# Bpod_Input.net
KiCad netlist of a schematic drawn in Altium Designer
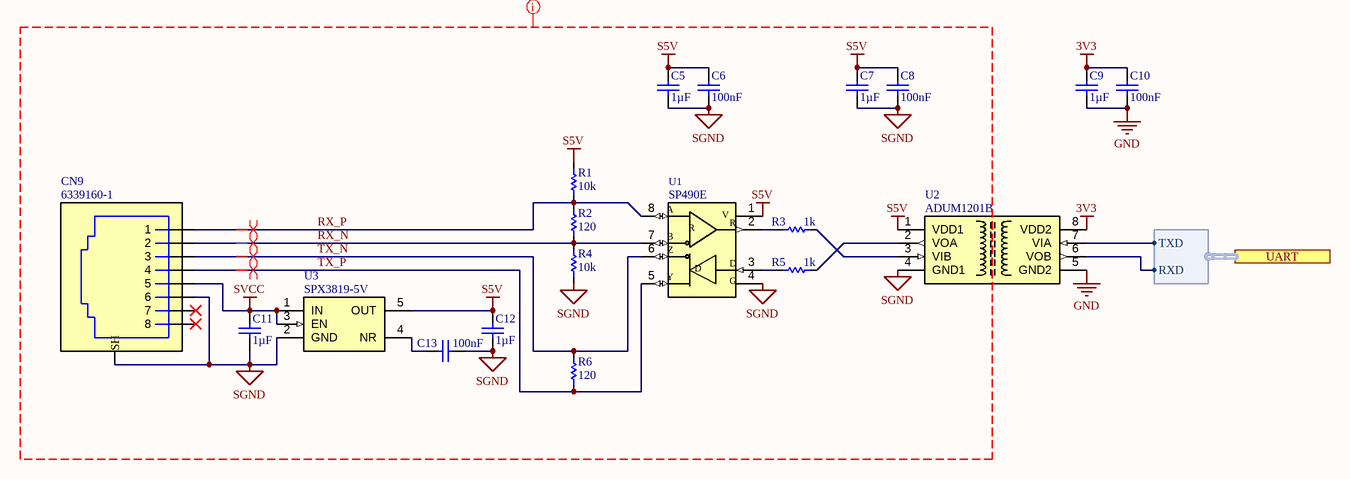
[diagram p0: Bpod Input.SchDoc]

(export (version "E")
  (design (tool "Eeschema 10.0.6"))
  (components
    (comp (ref "C5")
      (value "1µF")
      (footprint "CAP_CHIP_0603")
      (description "0603 Multilayer Ceramic Capacitors MLCC")
      (fields (field (name "PARTNUMBER") "CL10A105KB8NNNC") (field (name "TOLERANCE") "10%"))
      (libsource (lib "Sainsbury Wellcome Centre") (part "Cap"))
    )
    (comp (ref "C6")
      (value "100nF")
      (footprint "CAP_CHIP_0603")
      (description "0603 Multilayer Ceramic Capacitors MLCC")
      (fields (field (name "PARTNUMBER") "CC0603KRX7R9BB104") (field (name "TOLERANCE") "10%"))
      (libsource (lib "Sainsbury Wellcome Centre") (part "Cap"))
    )
    (comp (ref "C7")
      (value "1µF")
      (footprint "CAP_CHIP_0603")
      (description "0603 Multilayer Ceramic Capacitors MLCC")
      (fields (field (name "PARTNUMBER") "CL10A105KB8NNNC") (field (name "TOLERANCE") "10%"))
      (libsource (lib "Sainsbury Wellcome Centre") (part "Cap"))
    )
    (comp (ref "C8")
      (value "100nF")
      (footprint "CAP_CHIP_0603")
      (description "0603 Multilayer Ceramic Capacitors MLCC")
      (fields (field (name "PARTNUMBER") "CC0603KRX7R9BB104") (field (name "TOLERANCE") "10%"))
      (libsource (lib "Sainsbury Wellcome Centre") (part "Cap"))
    )
    (comp (ref "C9")
      (value "1µF")
      (footprint "CAP_CHIP_0603")
      (description "0603 Multilayer Ceramic Capacitors MLCC")
      (fields (field (name "PARTNUMBER") "CL10A105KB8NNNC") (field (name "TOLERANCE") "10%"))
      (libsource (lib "Sainsbury Wellcome Centre") (part "Cap"))
    )
    (comp (ref "C10")
      (value "100nF")
      (footprint "CAP_CHIP_0603")
      (description "0603 Multilayer Ceramic Capacitors MLCC")
      (fields (field (name "PARTNUMBER") "CC0603KRX7R9BB104") (field (name "TOLERANCE") "10%"))
      (libsource (lib "Sainsbury Wellcome Centre") (part "Cap"))
    )
    (comp (ref "C11")
      (value "1µF")
      (footprint "CAP_CHIP_0603")
      (description "0603 Multilayer Ceramic Capacitors MLCC")
      (fields (field (name "PARTNUMBER") "CL10A105KB8NNNC") (field (name "TOLERANCE") "10%"))
      (libsource (lib "Sainsbury Wellcome Centre") (part "Cap"))
    )
    (comp (ref "C12")
      (value "1µF")
      (footprint "CAP_CHIP_0603")
      (description "0603 Multilayer Ceramic Capacitors MLCC")
      (fields (field (name "PARTNUMBER") "CL10A105KB8NNNC") (field (name "TOLERANCE") "10%"))
      (libsource (lib "Sainsbury Wellcome Centre") (part "Cap"))
    )
    (comp (ref "C13")
      (value "100nF")
      (footprint "CAP_CHIP_0603")
      (description "0603 Multilayer Ceramic Capacitors MLCC")
      (fields (field (name "PARTNUMBER") "CC0603KRX7R9BB104") (field (name "TOLERANCE") "10%"))
      (libsource (lib "Sainsbury Wellcome Centre") (part "Cap"))
    )
    (comp (ref "CN9")
      (value "RJ45-6339160-1")
      (footprint "6339160-1")
      (description "CONN MOD JACK 8P8C R/A SHIELDED")
      (fields (field (name "PARTNUMBER") "6339160-1"))
      (libsource (lib "Sainsbury Wellcome Centre") (part "RJ45"))
    )
    (comp (ref "R1")
      (value "10k")
      (footprint "RES_CHIP_0603")
      (description "100mW Thick Film Resistors 75V ±100ppm/℃ ±1% 0603 Chip Resistor")
      (fields (field (name "PARTNUMBER") "0603WAF1002T5E") (field (name "TOLERANCE") "1%"))
      (libsource (lib "Sainsbury Wellcome Centre") (part "Res"))
    )
    (comp (ref "R2")
      (value "120")
      (footprint "RES_CHIP_0603")
      (description "100mW Thick Film Resistors 75V ±100ppm/℃ ±1% 0603 Chip Resistor")
      (fields (field (name "PARTNUMBER") "0603WAF1200T5E") (field (name "TOLERANCE") "1%"))
      (libsource (lib "Sainsbury Wellcome Centre") (part "Res"))
    )
    (comp (ref "R3")
      (value "1k")
      (footprint "RES_CHIP_0603")
      (description "100mW Thick Film Resistors 75V ±100ppm/℃ ±1% 0603 Chip Resistor")
      (fields (field (name "PARTNUMBER") "0603WAF1001T5E") (field (name "TOLERANCE") "1%"))
      (libsource (lib "Sainsbury Wellcome Centre") (part "Res"))
    )
    (comp (ref "R4")
      (value "10k")
      (footprint "RES_CHIP_0603")
      (description "100mW Thick Film Resistors 75V ±100ppm/℃ ±1% 0603 Chip Resistor")
      (fields (field (name "PARTNUMBER") "0603WAF1002T5E") (field (name "TOLERANCE") "1%"))
      (libsource (lib "Sainsbury Wellcome Centre") (part "Res"))
    )
    (comp (ref "R5")
      (value "1k")
      (footprint "RES_CHIP_0603")
      (description "100mW Thick Film Resistors 75V ±100ppm/℃ ±1% 0603 Chip Resistor")
      (fields (field (name "PARTNUMBER") "0603WAF1001T5E") (field (name "TOLERANCE") "1%"))
      (libsource (lib "Sainsbury Wellcome Centre") (part "Res"))
    )
    (comp (ref "R6")
      (value "120")
      (footprint "RES_CHIP_0603")
      (description "100mW Thick Film Resistors 75V ±100ppm/℃ ±1% 0603 Chip Resistor")
      (fields (field (name "PARTNUMBER") "0603WAF1200T5E") (field (name "TOLERANCE") "1%"))
      (libsource (lib "Sainsbury Wellcome Centre") (part "Res"))
    )
    (comp (ref "U1")
      (value "SP490E")
      (footprint "SOIC8")
      (fields (field (name "PARTNUMBER") "SP490EEN"))
      (libsource (lib "Sainsbury Wellcome Centre") (part "SP490E"))
    )
    (comp (ref "U2")
      (value "ADUM1201B")
      (footprint "SOIC8")
      (description "General Purpose Digital Isolator 2500Vrms 2 Channel 10Mbps 25kV/µs CMTI 8-SOIC (0.154")
      (fields (field (name "PARTNUMBER") "ADUM1201BRZ-RL7"))
      (libsource (lib "Sainsbury Wellcome Centre") (part "ADUM1201"))
    )
    (comp (ref "U3")
      (value "SPX3819-5V")
      (footprint "SOT23-5")
      (description "500mA 70dB Fixed 3.3V Positive electrode 16V LDO")
      (fields (field (name "PARTNUMBER") "SPX3819M5-L-5-0/TR"))
      (libsource (lib "Sainsbury Wellcome Centre") (part "LDO-5P-NR"))
    )
  )
  (nets
    (net (code "2") (name "/RXD") (class "Default")
      (node (ref "U2") (pin "6") (pinfunction "VOB_6") (pintype "output"))
    )
    (net (code "3") (name "/RX_N") (class "Default")
      (node (ref "CN9") (pin "2") (pinfunction "2_2") (pintype "passive"))
      (node (ref "R2") (pin "1") (pinfunction "1_1") (pintype "passive"))
      (node (ref "R4") (pin "2") (pinfunction "2_2") (pintype "passive"))
      (node (ref "U1") (pin "7") (pinfunction "B_7") (pintype "bidirectional"))
    )
    (net (code "4") (name "/RX_P") (class "Default")
      (node (ref "CN9") (pin "1") (pinfunction "1_1") (pintype "passive"))
      (node (ref "R1") (pin "1") (pinfunction "1_1") (pintype "passive"))
      (node (ref "R2") (pin "2") (pinfunction "2_2") (pintype "passive"))
      (node (ref "U1") (pin "8") (pinfunction "A_8") (pintype "bidirectional"))
    )
    (net (code "5") (name "/TXD") (class "Default")
      (node (ref "U2") (pin "7") (pinfunction "VIA_7") (pintype "input"))
    )
    (net (code "6") (name "/TX_N") (class "Default")
      (node (ref "CN9") (pin "3") (pinfunction "3_3") (pintype "passive"))
      (node (ref "R6") (pin "2") (pinfunction "2_2") (pintype "passive"))
      (node (ref "U1") (pin "6") (pinfunction "Z_6") (pintype "bidirectional"))
    )
    (net (code "7") (name "/TX_P") (class "Default")
      (node (ref "CN9") (pin "4") (pinfunction "4_4") (pintype "passive"))
      (node (ref "R6") (pin "1") (pinfunction "1_1") (pintype "passive"))
      (node (ref "U1") (pin "5") (pinfunction "Y_5") (pintype "bidirectional"))
    )
    (net (code "9") (name "3V3") (class "Default")
      (node (ref "C10") (pin "2") (pinfunction "2_2") (pintype "passive"))
      (node (ref "C9") (pin "2") (pinfunction "2_2") (pintype "passive"))
      (node (ref "U2") (pin "8") (pinfunction "VDD2_8") (pintype "power_in"))
    )
    (net (code "10") (name "GND") (class "Default")
      (node (ref "C10") (pin "1") (pinfunction "1_1") (pintype "passive"))
      (node (ref "C9") (pin "1") (pinfunction "1_1") (pintype "passive"))
      (node (ref "U2") (pin "5") (pinfunction "GND2_5") (pintype "power_in"))
    )
    (net (code "11") (name "Net-(U1-D)") (class "Default")
      (node (ref "R5") (pin "1") (pinfunction "1_1") (pintype "passive"))
      (node (ref "U1") (pin "3") (pinfunction "D_3") (pintype "input"))
    )
    (net (code "12") (name "Net-(U1-R)") (class "Default")
      (node (ref "R3") (pin "1") (pinfunction "1_1") (pintype "passive"))
      (node (ref "U1") (pin "2") (pinfunction "R_2") (pintype "output"))
    )
    (net (code "13") (name "Net-(U2-VIB)") (class "Default")
      (node (ref "R3") (pin "2") (pinfunction "2_2") (pintype "passive"))
      (node (ref "U2") (pin "3") (pinfunction "VIB_3") (pintype "input"))
    )
    (net (code "14") (name "Net-(U2-VOA)") (class "Default")
      (node (ref "R5") (pin "2") (pinfunction "2_2") (pintype "passive"))
      (node (ref "U2") (pin "2") (pinfunction "VOA_2") (pintype "output"))
    )
    (net (code "15") (name "Net-(U3-NR)") (class "Default")
      (node (ref "C13") (pin "2") (pinfunction "2_2") (pintype "passive"))
      (node (ref "U3") (pin "4") (pinfunction "NR_4") (pintype "passive"))
    )
    (net (code "16") (name "S5V") (class "Default")
      (node (ref "C12") (pin "2") (pinfunction "2_2") (pintype "passive"))
      (node (ref "C5") (pin "2") (pinfunction "2_2") (pintype "passive"))
      (node (ref "C6") (pin "2") (pinfunction "2_2") (pintype "passive"))
      (node (ref "C7") (pin "2") (pinfunction "2_2") (pintype "passive"))
      (node (ref "C8") (pin "2") (pinfunction "2_2") (pintype "passive"))
      (node (ref "R1") (pin "2") (pinfunction "2_2") (pintype "passive"))
      (node (ref "U1") (pin "1") (pinfunction "V_1") (pintype "power_in"))
      (node (ref "U2") (pin "1") (pinfunction "VDD1_1") (pintype "power_in"))
      (node (ref "U3") (pin "5") (pinfunction "OUT_5") (pintype "power_in"))
    )
    (net (code "17") (name "SGND") (class "Default")
      (node (ref "C11") (pin "1") (pinfunction "1_1") (pintype "passive"))
      (node (ref "C12") (pin "1") (pinfunction "1_1") (pintype "passive"))
      (node (ref "C13") (pin "1") (pinfunction "1_1") (pintype "passive"))
      (node (ref "C5") (pin "1") (pinfunction "1_1") (pintype "passive"))
      (node (ref "C6") (pin "1") (pinfunction "1_1") (pintype "passive"))
      (node (ref "C7") (pin "1") (pinfunction "1_1") (pintype "passive"))
      (node (ref "C8") (pin "1") (pinfunction "1_1") (pintype "passive"))
      (node (ref "CN9") (pin "0") (pinfunction "SH_0") (pintype "passive"))
      (node (ref "CN9") (pin "6") (pinfunction "6_6") (pintype "passive"))
      (node (ref "R4") (pin "1") (pinfunction "1_1") (pintype "passive"))
      (node (ref "U1") (pin "4") (pinfunction "G_4") (pintype "power_in"))
      (node (ref "U2") (pin "4") (pinfunction "GND1_4") (pintype "power_in"))
      (node (ref "U3") (pin "2") (pinfunction "GND_2") (pintype "power_in"))
    )
    (net (code "18") (name "SVCC") (class "Default")
      (node (ref "C11") (pin "2") (pinfunction "2_2") (pintype "passive"))
      (node (ref "CN9") (pin "5") (pinfunction "5_5") (pintype "passive"))
      (node (ref "U3") (pin "1") (pinfunction "IN_1") (pintype "power_in"))
      (node (ref "U3") (pin "3") (pinfunction "EN_3") (pintype "input"))
    )
    (net (code "19") (name "unconnected-(CN9-Pad7)") (class "Default")
      (node (ref "CN9") (pin "7") (pinfunction "7_7") (pintype "passive+no_connect"))
    )
    (net (code "20") (name "unconnected-(CN9-Pad8)") (class "Default")
      (node (ref "CN9") (pin "8") (pinfunction "8_8") (pintype "passive+no_connect"))
    )
  )
)
